# FLUKE_USB_IR.net
KiCad netlist of a schematic drawn in Altium Designer
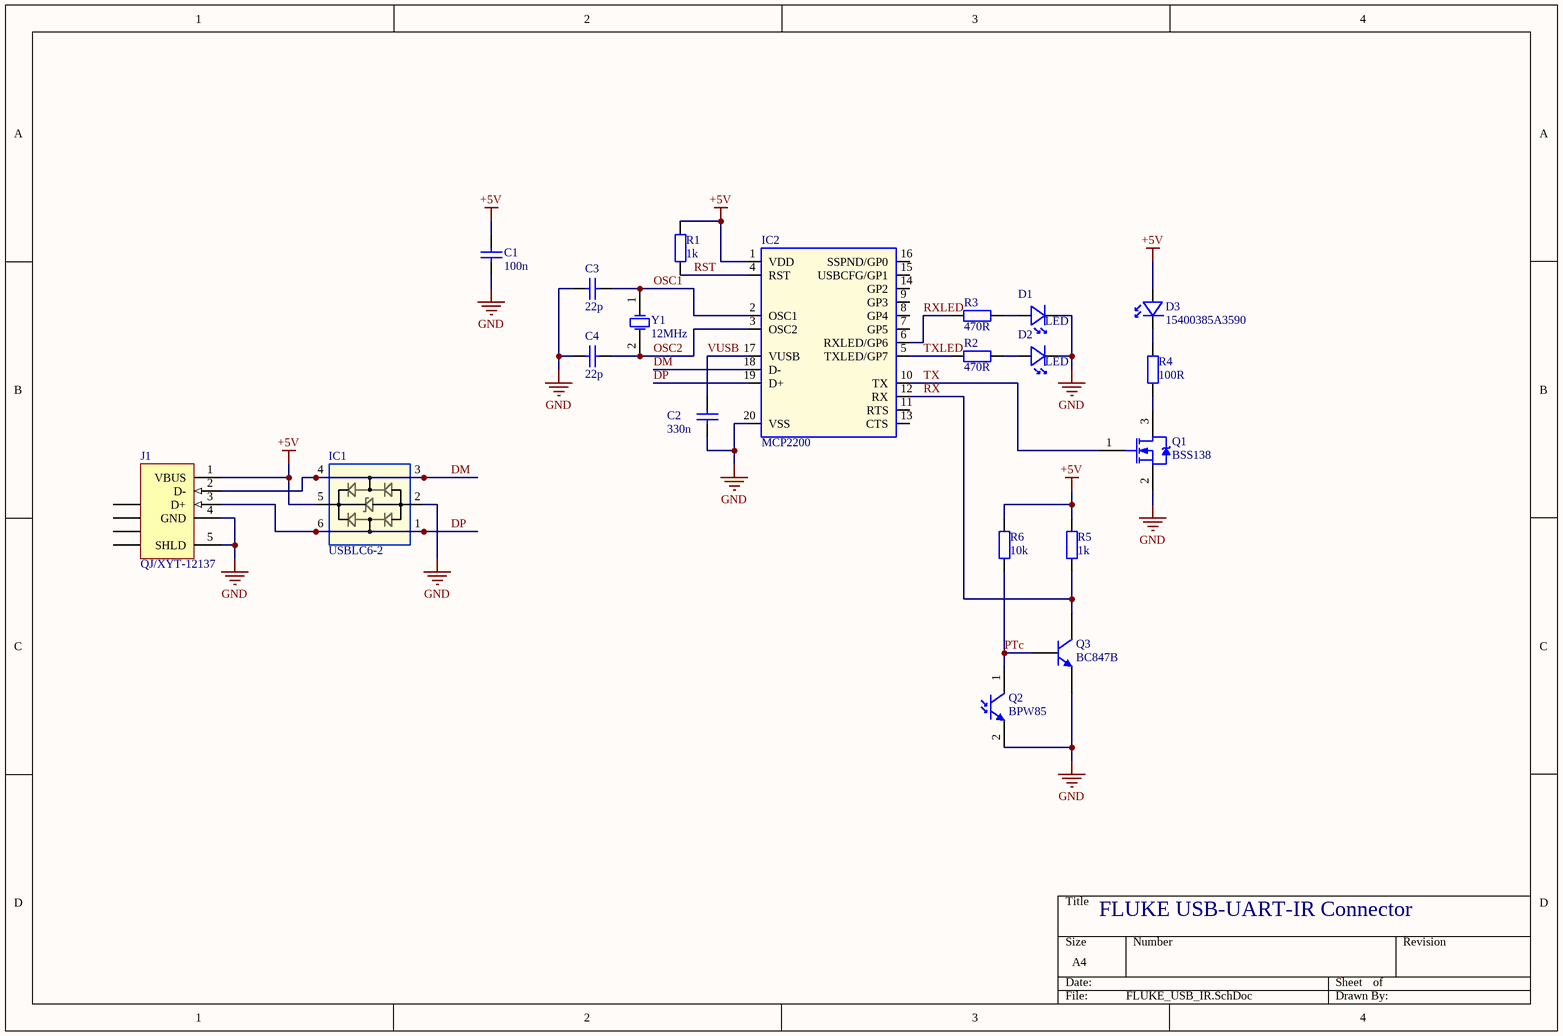
[diagram p0: FLUKE_USB_IR.SchDoc]

(export (version "E")
  (design (tool "Eeschema 10.0.6"))
  (components
    (comp (ref "C1")
      (value "100n")
      (footprint "0603")
      (description "Capacitor")
      (fields (field (name "Comment") "Cap") (field (name "PUBLISHER") "Altium Limited"))
      (libsource (lib "moje") (part "Cap"))
    )
    (comp (ref "C2")
      (value "330n")
      (footprint "0603")
      (description "Capacitor")
      (fields (field (name "Comment") "Cap") (field (name "PUBLISHER") "Altium Limited"))
      (libsource (lib "moje") (part "Cap"))
    )
    (comp (ref "C3")
      (value "22p")
      (footprint "0603")
      (description "Capacitor")
      (fields (field (name "Comment") "Cap") (field (name "PUBLISHER") "Altium Limited"))
      (libsource (lib "moje") (part "Cap"))
    )
    (comp (ref "C4")
      (value "22p")
      (footprint "0603")
      (description "Capacitor")
      (fields (field (name "Comment") "Cap") (field (name "PUBLISHER") "Altium Limited"))
      (libsource (lib "moje") (part "Cap"))
    )
    (comp (ref "D1") (value "LED") (footprint "0805") (libsource (lib "moje") (part "LED")))
    (comp (ref "D2") (value "LED") (footprint "0805") (libsource (lib "moje") (part "LED")))
    (comp (ref "D3") (value "15400385A3590") (footprint "LED_3MM") (libsource (lib "moje") (part "LED")))
    (comp (ref "IC1")
      (value "USBLC6-2")
      (footprint "SOT23-6")
      (description "Very low capacitance ESD protection diode array")
      (libsource (lib "moje") (part "USBLC6-2"))
    )
    (comp (ref "IC2")
      (value "MCP2200")
      (footprint "SOIC300-20_M")
      (description "USB 2.0 to UART Protocol Converter with GPIO")
      (libsource (lib "moje") (part "MCP2200"))
    )
    (comp (ref "J1")
      (value "QJ/XYT-12137")
      (footprint "440247")
      (description "USB 2.0, Right Angle, SMT, B Type, Receptacle, 5 Position, Black")
      (fields (field (name "PUBLISHER") "Altium Limited"))
      (libsource (lib "AMP Serial Bus USB") (part "440247-1"))
    )
    (comp (ref "Q1")
      (value "BSS138")
      (footprint "SOT23-3")
      (description "MOSFET SOT-23 N-CH LOGIC LEVEL")
      (fields (field (name "PUBLISHER") "Altium Limited"))
      (libsource (lib "moje") (part "BSS138"))
    )
    (comp (ref "Q2")
      (value "BPW85")
      (footprint "LED_3MM")
      (description "Phototransistor")
      (libsource (lib "moje") (part "Phototransistor"))
    )
    (comp (ref "Q3")
      (value "BC847B")
      (footprint "TO-236AB")
      (description "Bipolar Pro Electron")
      (fields (field (name "PUBLISHER") "Altium Limited"))
      (libsource (lib "NSC Discrete BJT") (part "BC847A"))
    )
    (comp (ref "R1")
      (value "1k")
      (footprint "0603")
      (description "Resistor")
      (fields (field (name "Comment") "Res") (field (name "PUBLISHER") "Altium Limited"))
      (libsource (lib "moje") (part "Res"))
    )
    (comp (ref "R2")
      (value "470R")
      (footprint "0603")
      (description "Resistor")
      (fields (field (name "Comment") "Res") (field (name "PUBLISHER") "Altium Limited"))
      (libsource (lib "") (part "Res_1"))
    )
    (comp (ref "R3")
      (value "470R")
      (footprint "0603")
      (description "Resistor")
      (fields (field (name "Comment") "Res") (field (name "PUBLISHER") "Altium Limited"))
      (libsource (lib "") (part "Res_1"))
    )
    (comp (ref "R4")
      (value "100R")
      (footprint "0603")
      (description "Resistor")
      (fields (field (name "Comment") "Res") (field (name "PUBLISHER") "Altium Limited"))
      (libsource (lib "moje") (part "Res"))
    )
    (comp (ref "R5")
      (value "1k")
      (footprint "0603")
      (description "Resistor")
      (fields (field (name "Comment") "Res") (field (name "PUBLISHER") "Altium Limited"))
      (libsource (lib "moje") (part "Res"))
    )
    (comp (ref "R6")
      (value "10k")
      (footprint "0603")
      (description "Resistor")
      (fields (field (name "Comment") "Res") (field (name "PUBLISHER") "Altium Limited"))
      (libsource (lib "moje") (part "Res"))
    )
    (comp (ref "Y1")
      (value "12MHz")
      (footprint "HC49/4H_SMX")
      (description "Surface Mount Quartz Crystal")
      (fields (field (name "PUBLISHER") "Altium Limited"))
      (libsource (lib "C-MAC Crystal Oscillator") (part "HC49/4H_SMX"))
    )
  )
  (nets
    (net (code "1") (name "+5V") (class "Default")
      (node (ref "C1") (pin "2") (pinfunction "2_2") (pintype "passive"))
      (node (ref "D3") (pin "1") (pinfunction "A_1") (pintype "passive"))
      (node (ref "IC1") (pin "5") (pinfunction "VP_5") (pintype "passive"))
      (node (ref "IC2") (pin "1") (pinfunction "VDD_1") (pintype "passive"))
      (node (ref "J1") (pin "1") (pinfunction "VBUS_1") (pintype "power_in"))
      (node (ref "R1") (pin "2") (pinfunction "2_2") (pintype "passive"))
      (node (ref "R5") (pin "2") (pinfunction "2_2") (pintype "passive"))
      (node (ref "R6") (pin "2") (pinfunction "2_2") (pintype "passive"))
    )
    (net (code "2") (name "/DM") (class "Default")
      (node (ref "IC1") (pin "3") (pinfunction "IO_3") (pintype "passive"))
      (node (ref "IC1") (pin "4") (pinfunction "IO_4") (pintype "passive"))
      (node (ref "IC2") (pin "18") (pinfunction "D-_18") (pintype "passive"))
      (node (ref "J1") (pin "2") (pinfunction "D-_2") (pintype "input"))
    )
    (net (code "3") (name "/DP") (class "Default")
      (node (ref "IC1") (pin "1") (pinfunction "IO_1") (pintype "passive"))
      (node (ref "IC1") (pin "6") (pinfunction "IO_6") (pintype "passive"))
      (node (ref "IC2") (pin "19") (pinfunction "D+_19") (pintype "passive"))
      (node (ref "J1") (pin "3") (pinfunction "D+_3") (pintype "input"))
    )
    (net (code "4") (name "/OSC1") (class "Default")
      (node (ref "C3") (pin "1") (pinfunction "1_1") (pintype "passive"))
      (node (ref "IC2") (pin "2") (pinfunction "OSC1_2") (pintype "passive"))
      (node (ref "Y1") (pin "1") (pinfunction "OSC1_1") (pintype "passive"))
    )
    (net (code "5") (name "/OSC2") (class "Default")
      (node (ref "C4") (pin "1") (pinfunction "1_1") (pintype "passive"))
      (node (ref "IC2") (pin "3") (pinfunction "OSC2_3") (pintype "passive"))
      (node (ref "Y1") (pin "2") (pinfunction "OSC2_2") (pintype "passive"))
    )
    (net (code "6") (name "/PTc") (class "Default")
      (node (ref "Q2") (pin "1") (pinfunction "C_1") (pintype "passive"))
      (node (ref "Q3") (pin "2") (pinfunction "B_2") (pintype "passive"))
      (node (ref "R6") (pin "1") (pinfunction "1_1") (pintype "passive"))
    )
    (net (code "7") (name "/RST") (class "Default")
      (node (ref "IC2") (pin "4") (pinfunction "RST_4") (pintype "passive"))
      (node (ref "R1") (pin "1") (pinfunction "1_1") (pintype "passive"))
    )
    (net (code "8") (name "/RX") (class "Default")
      (node (ref "IC2") (pin "12") (pinfunction "RX_12") (pintype "passive"))
      (node (ref "Q3") (pin "1") (pinfunction "C_1") (pintype "passive"))
      (node (ref "R5") (pin "1") (pinfunction "1_1") (pintype "passive"))
    )
    (net (code "9") (name "/RXLED") (class "Default")
      (node (ref "IC2") (pin "6") (pinfunction "RXLED/GP6_6") (pintype "passive"))
      (node (ref "R3") (pin "1") (pinfunction "1_1") (pintype "passive"))
    )
    (net (code "10") (name "/TX") (class "Default")
      (node (ref "IC2") (pin "10") (pinfunction "TX_10") (pintype "passive"))
      (node (ref "Q1") (pin "1") (pinfunction "G_1") (pintype "passive"))
    )
    (net (code "11") (name "/TXLED") (class "Default")
      (node (ref "IC2") (pin "5") (pinfunction "TXLED/GP7_5") (pintype "passive"))
      (node (ref "R2") (pin "1") (pinfunction "1_1") (pintype "passive"))
    )
    (net (code "12") (name "/VUSB") (class "Default")
      (node (ref "C2") (pin "2") (pinfunction "2_2") (pintype "passive"))
      (node (ref "IC2") (pin "17") (pinfunction "VUSB_17") (pintype "passive"))
    )
    (net (code "13") (name "GND") (class "Default")
      (node (ref "C1") (pin "1") (pinfunction "1_1") (pintype "passive"))
      (node (ref "C2") (pin "1") (pinfunction "1_1") (pintype "passive"))
      (node (ref "C3") (pin "2") (pinfunction "2_2") (pintype "passive"))
      (node (ref "C4") (pin "2") (pinfunction "2_2") (pintype "passive"))
      (node (ref "D1") (pin "2") (pinfunction "K_2") (pintype "passive"))
      (node (ref "D2") (pin "2") (pinfunction "K_2") (pintype "passive"))
      (node (ref "IC1") (pin "2") (pinfunction "VN_2") (pintype "passive"))
      (node (ref "IC2") (pin "20") (pinfunction "VSS_20") (pintype "passive"))
      (node (ref "J1") (pin "4") (pinfunction "GND_4") (pintype "power_in"))
      (node (ref "J1") (pin "5") (pinfunction "SHLD_5") (pintype "passive"))
      (node (ref "Q1") (pin "2") (pinfunction "S_2") (pintype "passive"))
      (node (ref "Q2") (pin "2") (pinfunction "E_2") (pintype "passive"))
      (node (ref "Q3") (pin "3") (pinfunction "E_3") (pintype "passive"))
    )
    (net (code "14") (name "Net-(D1-A)") (class "Default")
      (node (ref "D1") (pin "1") (pinfunction "A_1") (pintype "passive"))
      (node (ref "R3") (pin "2") (pinfunction "2_2") (pintype "passive"))
    )
    (net (code "15") (name "Net-(D2-A)") (class "Default")
      (node (ref "D2") (pin "1") (pinfunction "A_1") (pintype "passive"))
      (node (ref "R2") (pin "2") (pinfunction "2_2") (pintype "passive"))
    )
    (net (code "16") (name "Net-(D3-K)") (class "Default")
      (node (ref "D3") (pin "2") (pinfunction "K_2") (pintype "passive"))
      (node (ref "R4") (pin "2") (pinfunction "2_2") (pintype "passive"))
    )
    (net (code "17") (name "Net-(Q1-D)") (class "Default")
      (node (ref "Q1") (pin "3") (pinfunction "D_3") (pintype "passive"))
      (node (ref "R4") (pin "1") (pinfunction "1_1") (pintype "passive"))
    )
    (net (code "18") (name "unconnected-(IC2-CTS-Pad13)") (class "Default")
      (node (ref "IC2") (pin "13") (pinfunction "CTS_13") (pintype "passive"))
    )
    (net (code "19") (name "unconnected-(IC2-GP2-Pad14)") (class "Default")
      (node (ref "IC2") (pin "14") (pinfunction "GP2_14") (pintype "passive"))
    )
    (net (code "20") (name "unconnected-(IC2-GP3-Pad9)") (class "Default")
      (node (ref "IC2") (pin "9") (pinfunction "GP3_9") (pintype "passive"))
    )
    (net (code "21") (name "unconnected-(IC2-GP4-Pad8)") (class "Default")
      (node (ref "IC2") (pin "8") (pinfunction "GP4_8") (pintype "passive"))
    )
    (net (code "22") (name "unconnected-(IC2-GP5-Pad7)") (class "Default")
      (node (ref "IC2") (pin "7") (pinfunction "GP5_7") (pintype "passive"))
    )
    (net (code "23") (name "unconnected-(IC2-RTS-Pad11)") (class "Default")
      (node (ref "IC2") (pin "11") (pinfunction "RTS_11") (pintype "passive"))
    )
    (net (code "24") (name "unconnected-(IC2-SSPND{slash}GP0-Pad16)") (class "Default")
      (node (ref "IC2") (pin "16") (pinfunction "SSPND/GP0_16") (pintype "passive"))
    )
    (net (code "25") (name "unconnected-(IC2-USBCFG{slash}GP1-Pad15)") (class "Default")
      (node (ref "IC2") (pin "15") (pinfunction "USBCFG/GP1_15") (pintype "passive"))
    )
    (net (code "26") (name "unconnected-(J1-SHLD-Pad6)") (class "Default")
      (node (ref "J1") (pin "6") (pinfunction "SHLD_6") (pintype "passive"))
    )
    (net (code "27") (name "unconnected-(J1-SHLD-Pad7)") (class "Default")
      (node (ref "J1") (pin "7") (pinfunction "SHLD_7") (pintype "passive"))
    )
    (net (code "28") (name "unconnected-(J1-SHLD-Pad8)") (class "Default")
      (node (ref "J1") (pin "8") (pinfunction "SHLD_8") (pintype "passive"))
    )
    (net (code "29") (name "unconnected-(J1-SHLD-Pad9)") (class "Default")
      (node (ref "J1") (pin "9") (pinfunction "SHLD_9") (pintype "passive"))
    )
  )
)
